# Clock_Schematic_v_1.net
KiCad netlist of a schematic drawn in EAGLE
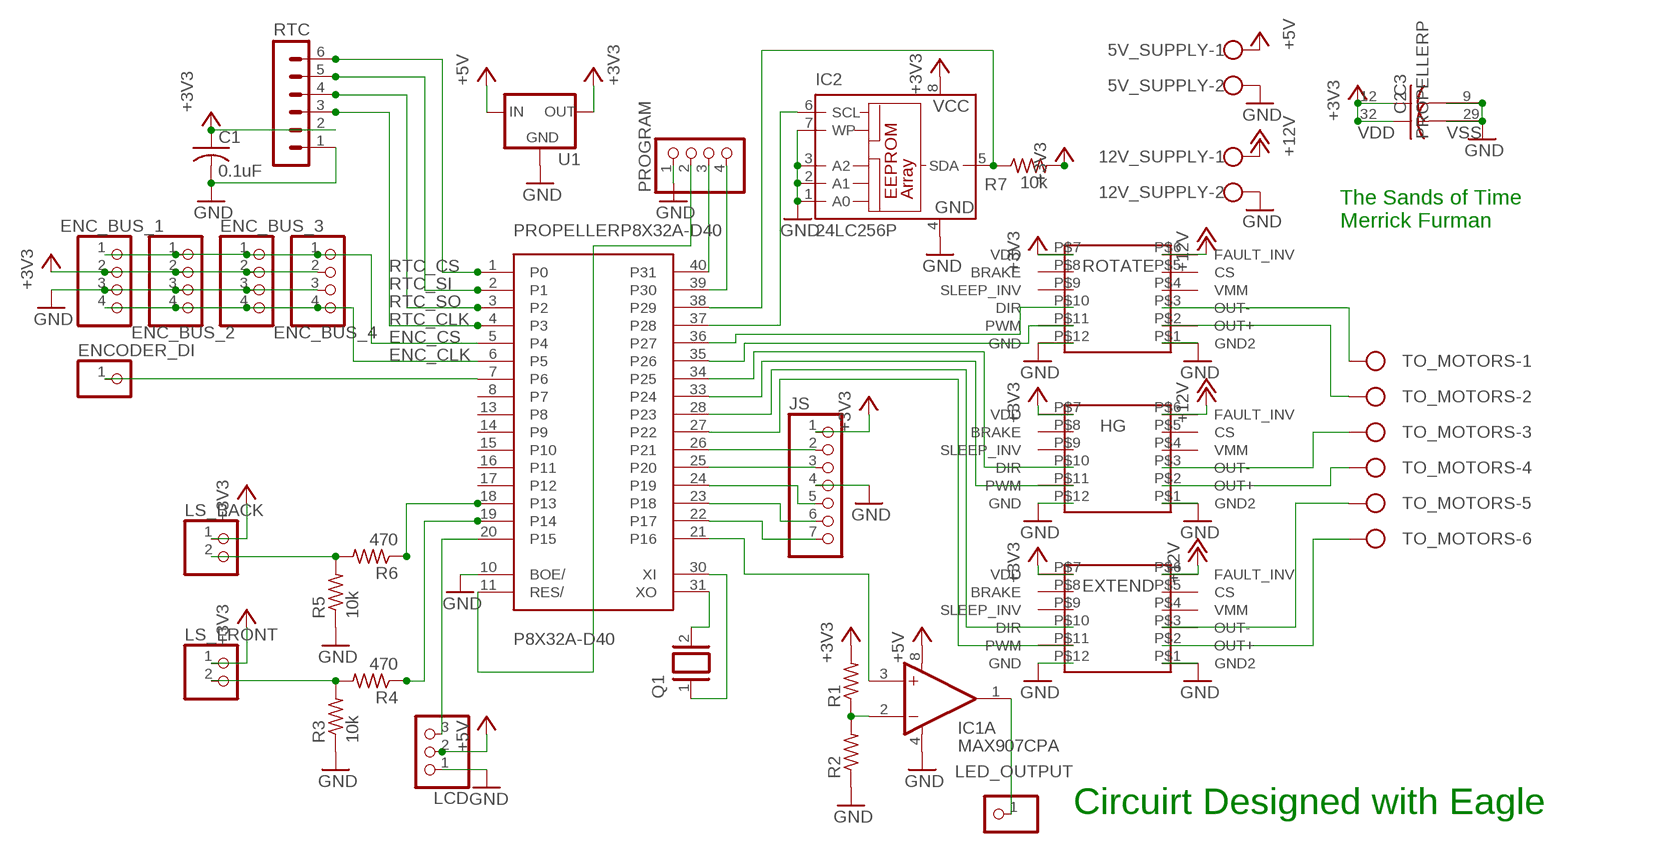
[diagram p0: schematic, sheet 1]

(export (version "E")
  (design (tool "Eeschema 10.0.6"))
  (components
    (comp (ref "5V_SUPPLY")
      (value "W237-102")
      (footprint "eagle-import:W237-102")
      (fields (field (name "MPN") "237-102"))
      (libsource (lib "eagle-import") (part "W237-102"))
    )
    (comp (ref "12V_SUPPLY")
      (value "W237-102")
      (footprint "eagle-import:W237-102")
      (fields (field (name "MPN") "237-102"))
      (libsource (lib "eagle-import") (part "W237-102"))
    )
    (comp (ref "C1")
      (value "0.1uF")
      (footprint "eagle-import:C050-025X075")
      (libsource (lib "eagle-import") (part "C-US050-025X075"))
    )
    (comp (ref "C2")
      (value "C-US050-025X075")
      (footprint "eagle-import:C050-025X075")
      (libsource (lib "eagle-import") (part "C-US050-025X075"))
    )
    (comp (ref "C3")
      (value "C-US050-025X075")
      (footprint "eagle-import:C050-025X075")
      (libsource (lib "eagle-import") (part "C-US050-025X075"))
    )
    (comp (ref "ENCODER_DI")
      (value "PINHD-1X1")
      (footprint "eagle-import:1X01")
      (libsource (lib "eagle-import") (part "PINHD-1X1"))
    )
    (comp (ref "ENC_BUS_1")
      (value "PINHD-1X4")
      (footprint "eagle-import:1X04")
      (libsource (lib "eagle-import") (part "PINHD-1X4"))
    )
    (comp (ref "ENC_BUS_2")
      (value "PINHD-1X4")
      (footprint "eagle-import:1X04")
      (libsource (lib "eagle-import") (part "PINHD-1X4"))
    )
    (comp (ref "ENC_BUS_3")
      (value "PINHD-1X4")
      (footprint "eagle-import:1X04")
      (libsource (lib "eagle-import") (part "PINHD-1X4"))
    )
    (comp (ref "ENC_BUS_4")
      (value "PINHD-1X4")
      (footprint "eagle-import:1X04")
      (libsource (lib "eagle-import") (part "PINHD-1X4"))
    )
    (comp (ref "EXTEND")
      (value "DRV")
      (footprint "eagle-import:DRV")
      (libsource (lib "eagle-import") (part "DRV"))
    )
    (comp (ref "HG")
      (value "DRV")
      (footprint "eagle-import:DRV")
      (libsource (lib "eagle-import") (part "DRV"))
    )
    (comp (ref "IC1")
      (value "MAX907CPA")
      (footprint "eagle-import:DIL08")
      (fields (field (name "MF") "MAXIM"))
      (libsource (lib "eagle-import") (part "MAX907CPA"))
    )
    (comp (ref "IC2")
      (value "24LC256P")
      (footprint "eagle-import:DIL8")
      (fields (field (name "MF") "MICROCHIP") (field (name "MPN") "24LC256-E/P"))
      (libsource (lib "eagle-import") (part "24PLC256"))
    )
    (comp (ref "JS")
      (value "PINHD-1X7")
      (footprint "eagle-import:1X07")
      (libsource (lib "eagle-import") (part "PINHD-1X7"))
    )
    (comp (ref "LCD")
      (value "PINHD-1X3")
      (footprint "eagle-import:1X03")
      (libsource (lib "eagle-import") (part "PINHD-1X3"))
    )
    (comp (ref "LED_OUTPUT")
      (value "PINHD-1X1")
      (footprint "eagle-import:1X01")
      (libsource (lib "eagle-import") (part "PINHD-1X1"))
    )
    (comp (ref "LS_BACK")
      (value "PINHD-1X2")
      (footprint "eagle-import:1X02")
      (libsource (lib "eagle-import") (part "PINHD-1X2"))
    )
    (comp (ref "LS_FRONT")
      (value "PINHD-1X2")
      (footprint "eagle-import:1X02")
      (libsource (lib "eagle-import") (part "PINHD-1X2"))
    )
    (comp (ref "PROGRAM")
      (value "PINHD-1X4")
      (footprint "eagle-import:1X04")
      (libsource (lib "eagle-import") (part "PINHD-1X4"))
    )
    (comp (ref "PROPELLER")
      (value "P8X32A-D40")
      (footprint "eagle-import:P8X32A-D40")
      (libsource (lib "eagle-import") (part "P8X32A-D40"))
    )
    (comp (ref "Q1")
      (value "XTAL/S")
      (footprint "eagle-import:QS")
      (libsource (lib "eagle-import") (part "XTAL/S"))
    )
    (comp (ref "R1")
      (value "R-US_0207/10")
      (footprint "eagle-import:0207_10")
      (libsource (lib "eagle-import") (part "R-US_0207/10"))
    )
    (comp (ref "R2")
      (value "R-US_0207/10")
      (footprint "eagle-import:0207_10")
      (libsource (lib "eagle-import") (part "R-US_0207/10"))
    )
    (comp (ref "R3")
      (value "10k")
      (footprint "eagle-import:0207_10")
      (libsource (lib "eagle-import") (part "R-US_0207/10"))
    )
    (comp (ref "R4")
      (value "470")
      (footprint "eagle-import:0207_10")
      (libsource (lib "eagle-import") (part "R-US_0207/10"))
    )
    (comp (ref "R5")
      (value "10k")
      (footprint "eagle-import:0207_10")
      (libsource (lib "eagle-import") (part "R-US_0207/10"))
    )
    (comp (ref "R6")
      (value "470")
      (footprint "eagle-import:0207_10")
      (libsource (lib "eagle-import") (part "R-US_0207/10"))
    )
    (comp (ref "R7")
      (value "10k")
      (footprint "eagle-import:0207_10")
      (libsource (lib "eagle-import") (part "R-US_0207/10"))
    )
    (comp (ref "ROTATE")
      (value "DRV")
      (footprint "eagle-import:DRV")
      (libsource (lib "eagle-import") (part "DRV"))
    )
    (comp (ref "RTC")
      (value "MA06-1")
      (footprint "eagle-import:MA06-1")
      (libsource (lib "eagle-import") (part "MA06-1"))
    )
    (comp (ref "TO_MOTORS")
      (value "W237-6")
      (footprint "eagle-import:W237-6")
      (libsource (lib "eagle-import") (part "W237-6"))
    )
    (comp (ref "U1")
      (value "V_REG_78XXSIDE")
      (footprint "eagle-import:78XXL")
      (libsource (lib "eagle-import") (part "V_REG_78XXSIDE"))
    )
  )
  (nets
    (net (code "1") (name "+3V3") (class "Default")
      (node (ref "C1") (pin "1") (pinfunction "1_1") (pintype "passive"))
      (node (ref "C2") (pin "1") (pinfunction "1_1") (pintype "passive"))
      (node (ref "C3") (pin "1") (pinfunction "1_1") (pintype "passive"))
      (node (ref "ENC_BUS_1") (pin "2") (pinfunction "2_2") (pintype "passive"))
      (node (ref "ENC_BUS_2") (pin "2") (pinfunction "2_2") (pintype "passive"))
      (node (ref "ENC_BUS_3") (pin "2") (pinfunction "2_2") (pintype "passive"))
      (node (ref "ENC_BUS_4") (pin "2") (pinfunction "2_2") (pintype "passive"))
      (node (ref "EXTEND") (pin "P$7") (pinfunction "VDD_P$7") (pintype "bidirectional"))
      (node (ref "HG") (pin "P$7") (pinfunction "VDD_P$7") (pintype "bidirectional"))
      (node (ref "IC2") (pin "8") (pinfunction "VCC_8") (pintype "power_in"))
      (node (ref "JS") (pin "1") (pinfunction "1_1") (pintype "passive"))
      (node (ref "LS_BACK") (pin "1") (pinfunction "1_1") (pintype "passive"))
      (node (ref "LS_FRONT") (pin "1") (pinfunction "1_1") (pintype "passive"))
      (node (ref "PROPELLER") (pin "12") (pinfunction "VDD_12") (pintype "power_in"))
      (node (ref "PROPELLER") (pin "32") (pinfunction "VDD_32") (pintype "power_in"))
      (node (ref "R1") (pin "2") (pinfunction "2_2") (pintype "passive"))
      (node (ref "R7") (pin "2") (pinfunction "2_2") (pintype "passive"))
      (node (ref "ROTATE") (pin "P$7") (pinfunction "VDD_P$7") (pintype "bidirectional"))
      (node (ref "RTC") (pin "2") (pinfunction "2_2") (pintype "passive"))
      (node (ref "U1") (pin "OUT") (pinfunction "OUT_OUT") (pintype "passive"))
    )
    (net (code "2") (name "+5V") (class "Default")
      (node (ref "5V_SUPPLY") (pin "1") (pinfunction "KL_1") (pintype "passive"))
      (node (ref "IC1") (pin "8") (pinfunction "V+_8") (pintype "power_in"))
      (node (ref "LCD") (pin "2") (pinfunction "2_2") (pintype "passive"))
      (node (ref "U1") (pin "IN") (pinfunction "IN_IN") (pintype "input"))
    )
    (net (code "3") (name "+12V") (class "Default")
      (node (ref "12V_SUPPLY") (pin "1") (pinfunction "KL_1") (pintype "passive"))
      (node (ref "EXTEND") (pin "P$6") (pinfunction "FAULT_INV_P$6") (pintype "bidirectional"))
      (node (ref "HG") (pin "P$6") (pinfunction "FAULT_INV_P$6") (pintype "bidirectional"))
      (node (ref "ROTATE") (pin "P$6") (pinfunction "FAULT_INV_P$6") (pintype "bidirectional"))
    )
    (net (code "4") (name "/ENC_CLK") (class "Default")
      (node (ref "ENC_BUS_1") (pin "4") (pinfunction "4_4") (pintype "passive"))
      (node (ref "ENC_BUS_2") (pin "4") (pinfunction "4_4") (pintype "passive"))
      (node (ref "ENC_BUS_3") (pin "4") (pinfunction "4_4") (pintype "passive"))
      (node (ref "ENC_BUS_4") (pin "4") (pinfunction "4_4") (pintype "passive"))
      (node (ref "PROPELLER") (pin "6") (pinfunction "P5_6") (pintype "bidirectional"))
    )
    (net (code "5") (name "/ENC_CS") (class "Default")
      (node (ref "ENC_BUS_1") (pin "1") (pinfunction "1_1") (pintype "passive"))
      (node (ref "ENC_BUS_2") (pin "1") (pinfunction "1_1") (pintype "passive"))
      (node (ref "ENC_BUS_3") (pin "1") (pinfunction "1_1") (pintype "passive"))
      (node (ref "ENC_BUS_4") (pin "1") (pinfunction "1_1") (pintype "passive"))
      (node (ref "PROPELLER") (pin "5") (pinfunction "P4_5") (pintype "bidirectional"))
    )
    (net (code "6") (name "/RTC_CLK") (class "Default")
      (node (ref "PROPELLER") (pin "4") (pinfunction "P3_4") (pintype "bidirectional"))
      (node (ref "RTC") (pin "3") (pinfunction "3_3") (pintype "passive"))
    )
    (net (code "7") (name "/RTC_CS") (class "Default")
      (node (ref "PROPELLER") (pin "1") (pinfunction "P0_1") (pintype "bidirectional"))
      (node (ref "RTC") (pin "6") (pinfunction "6_6") (pintype "passive"))
    )
    (net (code "8") (name "/RTC_SI") (class "Default")
      (node (ref "PROPELLER") (pin "2") (pinfunction "P1_2") (pintype "bidirectional"))
      (node (ref "RTC") (pin "5") (pinfunction "5_5") (pintype "passive"))
    )
    (net (code "9") (name "/RTC_SO") (class "Default")
      (node (ref "PROPELLER") (pin "3") (pinfunction "P2_3") (pintype "bidirectional"))
      (node (ref "RTC") (pin "4") (pinfunction "4_4") (pintype "passive"))
    )
    (net (code "10") (name "GND") (class "Default")
      (node (ref "12V_SUPPLY") (pin "2") (pinfunction "KL_2") (pintype "passive"))
      (node (ref "5V_SUPPLY") (pin "2") (pinfunction "KL_2") (pintype "passive"))
      (node (ref "C1") (pin "2") (pinfunction "2_2") (pintype "passive"))
      (node (ref "C2") (pin "2") (pinfunction "2_2") (pintype "passive"))
      (node (ref "C3") (pin "2") (pinfunction "2_2") (pintype "passive"))
      (node (ref "ENC_BUS_1") (pin "3") (pinfunction "3_3") (pintype "passive"))
      (node (ref "ENC_BUS_2") (pin "3") (pinfunction "3_3") (pintype "passive"))
      (node (ref "ENC_BUS_3") (pin "3") (pinfunction "3_3") (pintype "passive"))
      (node (ref "ENC_BUS_4") (pin "3") (pinfunction "3_3") (pintype "passive"))
      (node (ref "EXTEND") (pin "P$1") (pinfunction "GND2_P$1") (pintype "bidirectional"))
      (node (ref "EXTEND") (pin "P$12") (pinfunction "GND_P$12") (pintype "bidirectional"))
      (node (ref "HG") (pin "P$1") (pinfunction "GND2_P$1") (pintype "bidirectional"))
      (node (ref "HG") (pin "P$12") (pinfunction "GND_P$12") (pintype "bidirectional"))
      (node (ref "IC1") (pin "4") (pinfunction "V-_4") (pintype "power_in"))
      (node (ref "IC2") (pin "1") (pinfunction "A0_1") (pintype "input"))
      (node (ref "IC2") (pin "2") (pinfunction "A1_2") (pintype "input"))
      (node (ref "IC2") (pin "3") (pinfunction "A2_3") (pintype "input"))
      (node (ref "IC2") (pin "4") (pinfunction "GND_4") (pintype "power_in"))
      (node (ref "IC2") (pin "7") (pinfunction "WP_7") (pintype "input"))
      (node (ref "JS") (pin "4") (pinfunction "4_4") (pintype "passive"))
      (node (ref "LCD") (pin "1") (pinfunction "1_1") (pintype "passive"))
      (node (ref "PROGRAM") (pin "1") (pinfunction "1_1") (pintype "passive"))
      (node (ref "PROPELLER") (pin "10") (pinfunction "BOE/_10") (pintype "input"))
      (node (ref "PROPELLER") (pin "29") (pinfunction "VSS_29") (pintype "power_in"))
      (node (ref "PROPELLER") (pin "9") (pinfunction "VSS_9") (pintype "power_in"))
      (node (ref "R2") (pin "1") (pinfunction "1_1") (pintype "passive"))
      (node (ref "R3") (pin "1") (pinfunction "1_1") (pintype "passive"))
      (node (ref "R5") (pin "1") (pinfunction "1_1") (pintype "passive"))
      (node (ref "ROTATE") (pin "P$1") (pinfunction "GND2_P$1") (pintype "bidirectional"))
      (node (ref "ROTATE") (pin "P$12") (pinfunction "GND_P$12") (pintype "bidirectional"))
      (node (ref "RTC") (pin "1") (pinfunction "1_1") (pintype "passive"))
      (node (ref "U1") (pin "GND") (pinfunction "GND_GND") (pintype "input"))
    )
    (net (code "11") (name "Net-(EXTEND-DIR)") (class "Default")
      (node (ref "EXTEND") (pin "P$10") (pinfunction "DIR_P$10") (pintype "bidirectional"))
      (node (ref "PROPELLER") (pin "28") (pinfunction "P23_28") (pintype "bidirectional"))
    )
    (net (code "12") (name "Net-(EXTEND-OUT+)") (class "Default")
      (node (ref "EXTEND") (pin "P$2") (pinfunction "OUT+_P$2") (pintype "bidirectional"))
      (node (ref "TO_MOTORS") (pin "6") (pinfunction "KL_6") (pintype "passive"))
    )
    (net (code "13") (name "Net-(EXTEND-OUT-)") (class "Default")
      (node (ref "EXTEND") (pin "P$3") (pinfunction "OUT-_P$3") (pintype "bidirectional"))
      (node (ref "TO_MOTORS") (pin "5") (pinfunction "KL_5") (pintype "passive"))
    )
    (net (code "14") (name "Net-(EXTEND-PWM)") (class "Default")
      (node (ref "EXTEND") (pin "P$11") (pinfunction "PWM_P$11") (pintype "bidirectional"))
      (node (ref "PROPELLER") (pin "27") (pinfunction "P22_27") (pintype "bidirectional"))
    )
    (net (code "15") (name "Net-(HG-DIR)") (class "Default")
      (node (ref "HG") (pin "P$10") (pinfunction "DIR_P$10") (pintype "bidirectional"))
      (node (ref "PROPELLER") (pin "34") (pinfunction "P25_34") (pintype "bidirectional"))
    )
    (net (code "16") (name "Net-(HG-OUT+)") (class "Default")
      (node (ref "HG") (pin "P$2") (pinfunction "OUT+_P$2") (pintype "bidirectional"))
      (node (ref "TO_MOTORS") (pin "4") (pinfunction "KL_4") (pintype "passive"))
    )
    (net (code "17") (name "Net-(HG-OUT-)") (class "Default")
      (node (ref "HG") (pin "P$3") (pinfunction "OUT-_P$3") (pintype "bidirectional"))
      (node (ref "TO_MOTORS") (pin "3") (pinfunction "KL_3") (pintype "passive"))
    )
    (net (code "18") (name "Net-(HG-PWM)") (class "Default")
      (node (ref "HG") (pin "P$11") (pinfunction "PWM_P$11") (pintype "bidirectional"))
      (node (ref "PROPELLER") (pin "33") (pinfunction "P24_33") (pintype "bidirectional"))
    )
    (net (code "19") (name "Net-(IC1A-+IN)") (class "Default")
      (node (ref "IC1") (pin "3") (pinfunction "+IN_3") (pintype "input"))
      (node (ref "PROPELLER") (pin "21") (pinfunction "P16_21") (pintype "bidirectional"))
    )
    (net (code "20") (name "Net-(IC1A--IN)") (class "Default")
      (node (ref "IC1") (pin "2") (pinfunction "-IN_2") (pintype "input"))
      (node (ref "R1") (pin "1") (pinfunction "1_1") (pintype "passive"))
      (node (ref "R2") (pin "2") (pinfunction "2_2") (pintype "passive"))
    )
    (net (code "21") (name "Net-(IC1A-OUT)") (class "Default")
      (node (ref "IC1") (pin "1") (pinfunction "OUT_1") (pintype "output"))
      (node (ref "LED_OUTPUT") (pin "1") (pinfunction "1_1") (pintype "passive"))
    )
    (net (code "22") (name "Net-(IC2-SCL)") (class "Default")
      (node (ref "IC2") (pin "6") (pinfunction "SCL_6") (pintype "input"))
      (node (ref "PROPELLER") (pin "37") (pinfunction "P28_37") (pintype "bidirectional"))
    )
    (net (code "23") (name "Net-(IC2-SDA)") (class "Default")
      (node (ref "IC2") (pin "5") (pinfunction "SDA_5") (pintype "bidirectional"))
      (node (ref "PROPELLER") (pin "38") (pinfunction "P29_38") (pintype "bidirectional"))
      (node (ref "R7") (pin "1") (pinfunction "1_1") (pintype "passive"))
    )
    (net (code "24") (name "Net-(LS_BACK-Pad2)") (class "Default")
      (node (ref "LS_BACK") (pin "2") (pinfunction "2_2") (pintype "passive"))
      (node (ref "R5") (pin "2") (pinfunction "2_2") (pintype "passive"))
      (node (ref "R6") (pin "2") (pinfunction "2_2") (pintype "passive"))
    )
    (net (code "25") (name "Net-(LS_FRONT-Pad2)") (class "Default")
      (node (ref "LS_FRONT") (pin "2") (pinfunction "2_2") (pintype "passive"))
      (node (ref "R3") (pin "2") (pinfunction "2_2") (pintype "passive"))
      (node (ref "R4") (pin "2") (pinfunction "2_2") (pintype "passive"))
    )
    (net (code "26") (name "Net-(PROPELLERB-P6)") (class "Default")
      (node (ref "ENCODER_DI") (pin "1") (pinfunction "1_1") (pintype "passive"))
      (node (ref "PROPELLER") (pin "7") (pinfunction "P6_7") (pintype "bidirectional"))
    )
    (net (code "27") (name "Net-(PROPELLERB-P13)") (class "Default")
      (node (ref "PROPELLER") (pin "18") (pinfunction "P13_18") (pintype "bidirectional"))
      (node (ref "R6") (pin "1") (pinfunction "1_1") (pintype "passive"))
    )
    (net (code "28") (name "Net-(PROPELLERB-P14)") (class "Default")
      (node (ref "PROPELLER") (pin "19") (pinfunction "P14_19") (pintype "bidirectional"))
      (node (ref "R4") (pin "1") (pinfunction "1_1") (pintype "passive"))
    )
    (net (code "29") (name "Net-(PROPELLERB-P15)") (class "Default")
      (node (ref "LCD") (pin "3") (pinfunction "3_3") (pintype "passive"))
      (node (ref "PROPELLER") (pin "20") (pinfunction "P15_20") (pintype "bidirectional"))
    )
    (net (code "30") (name "Net-(PROPELLERB-P17)") (class "Default")
      (node (ref "JS") (pin "7") (pinfunction "7_7") (pintype "passive"))
      (node (ref "PROPELLER") (pin "22") (pinfunction "P17_22") (pintype "bidirectional"))
    )
    (net (code "31") (name "Net-(PROPELLERB-P18)") (class "Default")
      (node (ref "JS") (pin "6") (pinfunction "6_6") (pintype "passive"))
      (node (ref "PROPELLER") (pin "23") (pinfunction "P18_23") (pintype "bidirectional"))
    )
    (net (code "32") (name "Net-(PROPELLERB-P19)") (class "Default")
      (node (ref "JS") (pin "5") (pinfunction "5_5") (pintype "passive"))
      (node (ref "PROPELLER") (pin "24") (pinfunction "P19_24") (pintype "bidirectional"))
    )
    (net (code "33") (name "Net-(PROPELLERB-P20)") (class "Default")
      (node (ref "JS") (pin "3") (pinfunction "3_3") (pintype "passive"))
      (node (ref "PROPELLER") (pin "25") (pinfunction "P20_25") (pintype "bidirectional"))
    )
    (net (code "34") (name "Net-(PROPELLERB-P21)") (class "Default")
      (node (ref "JS") (pin "2") (pinfunction "2_2") (pintype "passive"))
      (node (ref "PROPELLER") (pin "26") (pinfunction "P21_26") (pintype "bidirectional"))
    )
    (net (code "35") (name "Net-(PROPELLERB-P26)") (class "Default")
      (node (ref "PROPELLER") (pin "35") (pinfunction "P26_35") (pintype "bidirectional"))
      (node (ref "ROTATE") (pin "P$11") (pinfunction "PWM_P$11") (pintype "bidirectional"))
    )
    (net (code "36") (name "Net-(PROPELLERB-P27)") (class "Default")
      (node (ref "PROPELLER") (pin "36") (pinfunction "P27_36") (pintype "bidirectional"))
      (node (ref "ROTATE") (pin "P$10") (pinfunction "DIR_P$10") (pintype "bidirectional"))
    )
    (net (code "37") (name "Net-(PROPELLERB-P30)") (class "Default")
      (node (ref "PROGRAM") (pin "4") (pinfunction "4_4") (pintype "passive"))
      (node (ref "PROPELLER") (pin "39") (pinfunction "P30_39") (pintype "bidirectional"))
    )
    (net (code "38") (name "Net-(PROPELLERB-P31)") (class "Default")
      (node (ref "PROGRAM") (pin "3") (pinfunction "3_3") (pintype "passive"))
      (node (ref "PROPELLER") (pin "40") (pinfunction "P31_40") (pintype "bidirectional"))
    )
    (net (code "39") (name "Net-(PROPELLERB-RES{slash})") (class "Default")
      (node (ref "PROGRAM") (pin "2") (pinfunction "2_2") (pintype "passive"))
      (node (ref "PROPELLER") (pin "11") (pinfunction "RES/_11") (pintype "bidirectional"))
    )
    (net (code "40") (name "Net-(PROPELLERB-XI)") (class "Default")
      (node (ref "PROPELLER") (pin "30") (pinfunction "XI_30") (pintype "input"))
      (node (ref "Q1") (pin "1") (pinfunction "1_1") (pintype "passive"))
    )
    (net (code "41") (name "Net-(PROPELLERB-XO)") (class "Default")
      (node (ref "PROPELLER") (pin "31") (pinfunction "XO_31") (pintype "output"))
      (node (ref "Q1") (pin "2") (pinfunction "2_2") (pintype "passive"))
    )
    (net (code "42") (name "Net-(ROTATE-OUT+)") (class "Default")
      (node (ref "ROTATE") (pin "P$2") (pinfunction "OUT+_P$2") (pintype "bidirectional"))
      (node (ref "TO_MOTORS") (pin "2") (pinfunction "KL_2") (pintype "passive"))
    )
    (net (code "43") (name "Net-(ROTATE-OUT-)") (class "Default")
      (node (ref "ROTATE") (pin "P$3") (pinfunction "OUT-_P$3") (pintype "bidirectional"))
      (node (ref "TO_MOTORS") (pin "1") (pinfunction "KL_1") (pintype "passive"))
    )
    (net (code "44") (name "unconnected-(EXTEND-BRAKE-PadP$8)") (class "Default")
      (node (ref "EXTEND") (pin "P$8") (pinfunction "BRAKE_P$8") (pintype "bidirectional"))
    )
    (net (code "45") (name "unconnected-(EXTEND-CS-PadP$5)") (class "Default")
      (node (ref "EXTEND") (pin "P$5") (pinfunction "CS_P$5") (pintype "bidirectional"))
    )
    (net (code "46") (name "unconnected-(EXTEND-SLEEP_INV-PadP$9)") (class "Default")
      (node (ref "EXTEND") (pin "P$9") (pinfunction "SLEEP_INV_P$9") (pintype "bidirectional"))
    )
    (net (code "47") (name "unconnected-(EXTEND-VMM-PadP$4)") (class "Default")
      (node (ref "EXTEND") (pin "P$4") (pinfunction "VMM_P$4") (pintype "bidirectional"))
    )
    (net (code "48") (name "unconnected-(HG-BRAKE-PadP$8)") (class "Default")
      (node (ref "HG") (pin "P$8") (pinfunction "BRAKE_P$8") (pintype "bidirectional"))
    )
    (net (code "49") (name "unconnected-(HG-CS-PadP$5)") (class "Default")
      (node (ref "HG") (pin "P$5") (pinfunction "CS_P$5") (pintype "bidirectional"))
    )
    (net (code "50") (name "unconnected-(HG-SLEEP_INV-PadP$9)") (class "Default")
      (node (ref "HG") (pin "P$9") (pinfunction "SLEEP_INV_P$9") (pintype "bidirectional"))
    )
    (net (code "51") (name "unconnected-(HG-VMM-PadP$4)") (class "Default")
      (node (ref "HG") (pin "P$4") (pinfunction "VMM_P$4") (pintype "bidirectional"))
    )
    (net (code "52") (name "unconnected-(PROPELLERB-P7-Pad8)") (class "Default")
      (node (ref "PROPELLER") (pin "8") (pinfunction "P7_8") (pintype "bidirectional"))
    )
    (net (code "53") (name "unconnected-(PROPELLERB-P8-Pad13)") (class "Default")
      (node (ref "PROPELLER") (pin "13") (pinfunction "P8_13") (pintype "bidirectional"))
    )
    (net (code "54") (name "unconnected-(PROPELLERB-P9-Pad14)") (class "Default")
      (node (ref "PROPELLER") (pin "14") (pinfunction "P9_14") (pintype "bidirectional"))
    )
    (net (code "55") (name "unconnected-(PROPELLERB-P10-Pad15)") (class "Default")
      (node (ref "PROPELLER") (pin "15") (pinfunction "P10_15") (pintype "bidirectional"))
    )
    (net (code "56") (name "unconnected-(PROPELLERB-P11-Pad16)") (class "Default")
      (node (ref "PROPELLER") (pin "16") (pinfunction "P11_16") (pintype "bidirectional"))
    )
    (net (code "57") (name "unconnected-(PROPELLERB-P12-Pad17)") (class "Default")
      (node (ref "PROPELLER") (pin "17") (pinfunction "P12_17") (pintype "bidirectional"))
    )
    (net (code "58") (name "unconnected-(ROTATE-BRAKE-PadP$8)") (class "Default")
      (node (ref "ROTATE") (pin "P$8") (pinfunction "BRAKE_P$8") (pintype "bidirectional"))
    )
    (net (code "59") (name "unconnected-(ROTATE-CS-PadP$5)") (class "Default")
      (node (ref "ROTATE") (pin "P$5") (pinfunction "CS_P$5") (pintype "bidirectional"))
    )
    (net (code "60") (name "unconnected-(ROTATE-SLEEP_INV-PadP$9)") (class "Default")
      (node (ref "ROTATE") (pin "P$9") (pinfunction "SLEEP_INV_P$9") (pintype "bidirectional"))
    )
    (net (code "61") (name "unconnected-(ROTATE-VMM-PadP$4)") (class "Default")
      (node (ref "ROTATE") (pin "P$4") (pinfunction "VMM_P$4") (pintype "bidirectional"))
    )
  )
)
